# pt100.net
KiCad netlist of a schematic drawn in Altium Designer
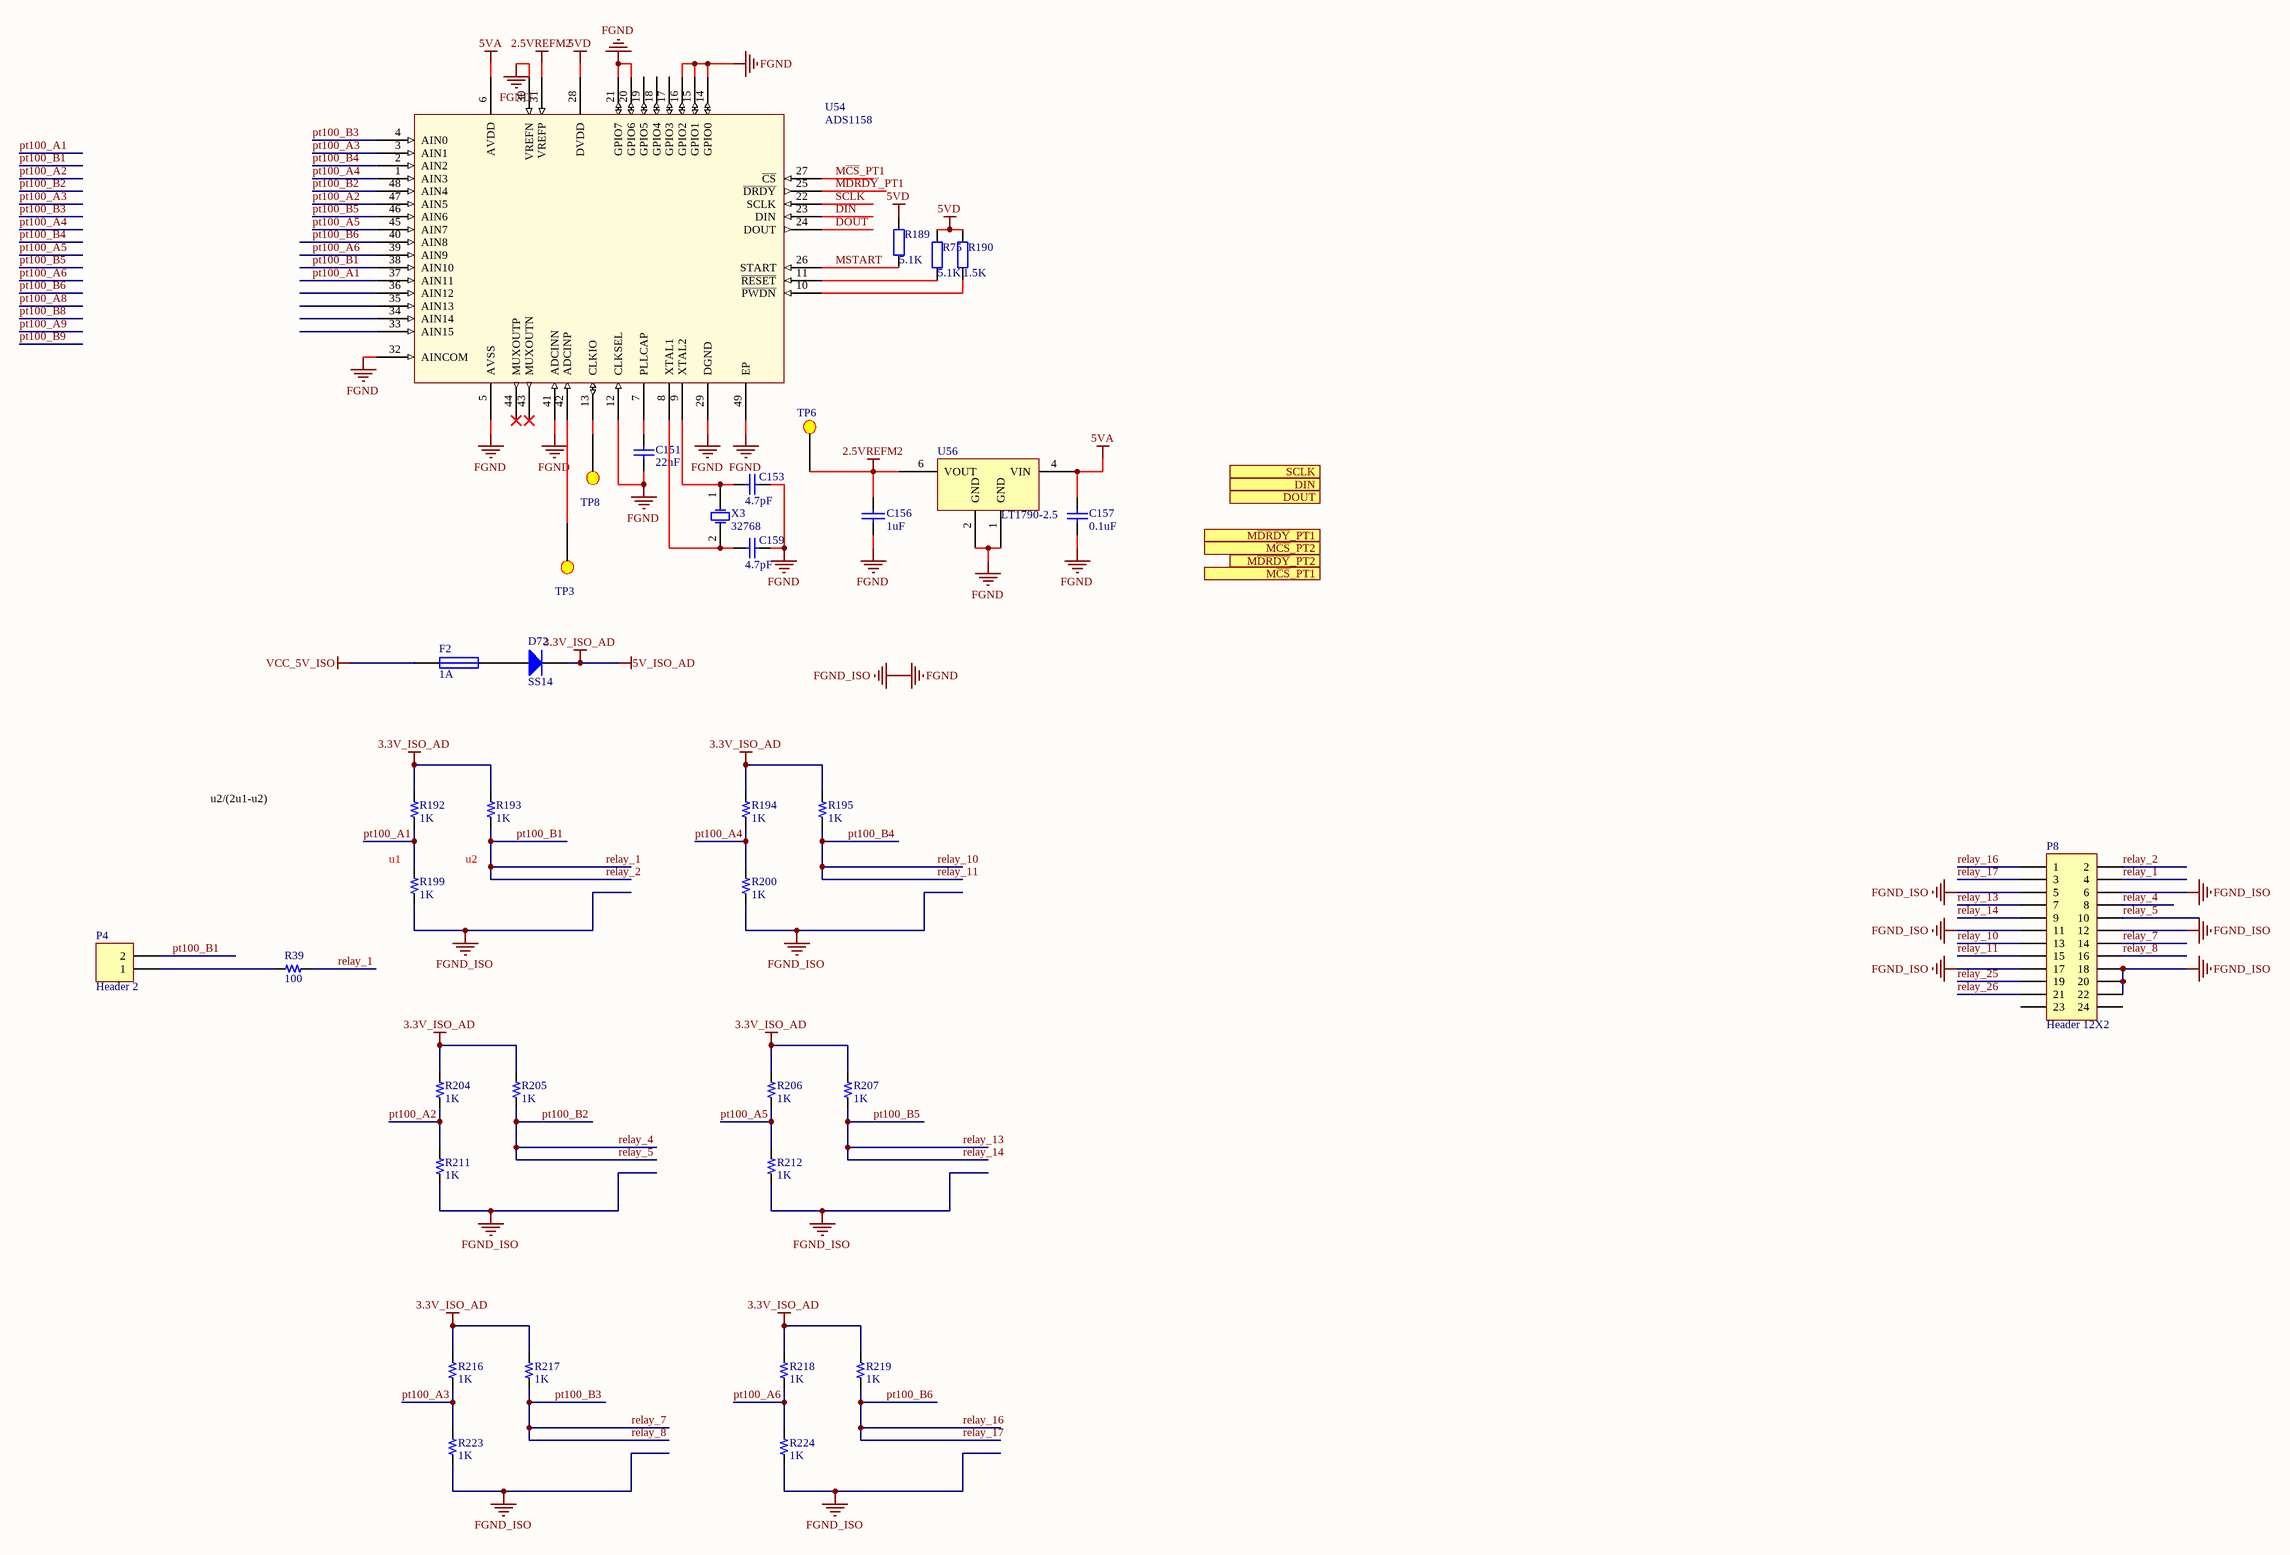
[diagram p0: pt100.SchDoc]

(export (version "E")
  (design (tool "Eeschema 10.0.6"))
  (components
    (comp (ref "C151")
      (value "22nF")
      (footprint "0805C")
      (description "Capacitor")
      (fields (field (name "PUBLISHER") "Altium Limited"))
      (libsource (lib "Miscellaneous Devices") (part "Cap"))
    )
    (comp (ref "C153")
      (value "4.7pF")
      (footprint "0603C")
      (description "Capacitor")
      (fields (field (name "PUBLISHER") "Altium Limited"))
      (libsource (lib "Miscellaneous Devices") (part "Cap"))
    )
    (comp (ref "C156")
      (value "1uF")
      (footprint "0603C")
      (description "Capacitor")
      (libsource (lib "*") (part "CAP"))
    )
    (comp (ref "C157")
      (value "0.1uF")
      (footprint "0603C")
      (description "Capacitor")
      (fields (field (name "PUBLISHER") "Altium Limited"))
      (libsource (lib "Miscellaneous Devices") (part "Cap"))
    )
    (comp (ref "C159")
      (value "4.7pF")
      (footprint "0603C")
      (description "Capacitor")
      (fields (field (name "PUBLISHER") "Altium Limited"))
      (libsource (lib "Miscellaneous Devices") (part "Cap"))
    )
    (comp (ref "D72")
      (value "SS14")
      (footprint "DO-214AC")
      (description "Default Diode")
      (fields (field (name "PUBLISHER") "Altium Limited"))
      (libsource (lib "Miscellaneous Devices") (part "Diode"))
    )
    (comp (ref "F2")
      (value "1A")
      (footprint "0805r")
      (description "Fuse")
      (fields (field (name "PUBLISHER") "Altium Limited"))
      (libsource (lib "Miscellaneous Devices") (part "Fuse 1"))
    )
    (comp (ref "P4")
      (value "Header 2")
      (footprint "HDR1X2")
      (description "Header, 2-Pin")
      (fields (field (name "PUBLISHER") "Altium Limited"))
      (libsource (lib "Miscellaneous Connectors") (part "Header 2"))
    )
    (comp (ref "P8")
      (value "Header 12X2")
      (footprint "controller_V1.1:XH2.54_2x12")
      (description "Header, 12-Pin, Dual row")
      (fields (field (name "PUBLISHER") "Altium Limited"))
      (libsource (lib "Miscellaneous Connectors") (part "Header 12X2"))
    )
    (comp (ref "R39")
      (value "100")
      (footprint "0603R")
      (description "R")
      (libsource (lib "JRJ_1") (part "R"))
    )
    (comp (ref "R75") (value "5.1K") (footprint "0603R") (libsource (lib "MQlibrary") (part "Res0805M")))
    (comp (ref "R189") (value "5.1K") (footprint "0603R") (libsource (lib "MQlibrary") (part "Res0805M")))
    (comp (ref "R190") (value "1.5K") (footprint "0603R") (libsource (lib "MQlibrary") (part "Res0805M")))
    (comp (ref "R192")
      (value "1K")
      (footprint "0603R")
      (description "R")
      (libsource (lib "JRJ_1") (part "R"))
    )
    (comp (ref "R193")
      (value "1K")
      (footprint "0603R")
      (description "R")
      (libsource (lib "JRJ_1") (part "R"))
    )
    (comp (ref "R194")
      (value "1K")
      (footprint "0603R")
      (description "R")
      (libsource (lib "JRJ_1") (part "R"))
    )
    (comp (ref "R195")
      (value "1K")
      (footprint "0603R")
      (description "R")
      (libsource (lib "JRJ_1") (part "R"))
    )
    (comp (ref "R199")
      (value "1K")
      (footprint "0603R")
      (description "R")
      (libsource (lib "JRJ_1") (part "R"))
    )
    (comp (ref "R200")
      (value "1K")
      (footprint "0603R")
      (description "R")
      (libsource (lib "JRJ_1") (part "R"))
    )
    (comp (ref "R204")
      (value "1K")
      (footprint "0603R")
      (description "R")
      (libsource (lib "JRJ_1") (part "R"))
    )
    (comp (ref "R205")
      (value "1K")
      (footprint "0603R")
      (description "R")
      (libsource (lib "JRJ_1") (part "R"))
    )
    (comp (ref "R206")
      (value "1K")
      (footprint "0603R")
      (description "R")
      (libsource (lib "JRJ_1") (part "R"))
    )
    (comp (ref "R207")
      (value "1K")
      (footprint "0603R")
      (description "R")
      (libsource (lib "JRJ_1") (part "R"))
    )
    (comp (ref "R211")
      (value "1K")
      (footprint "0603R")
      (description "R")
      (libsource (lib "JRJ_1") (part "R"))
    )
    (comp (ref "R212")
      (value "1K")
      (footprint "0603R")
      (description "R")
      (libsource (lib "JRJ_1") (part "R"))
    )
    (comp (ref "R216")
      (value "1K")
      (footprint "0603R")
      (description "R")
      (libsource (lib "JRJ_1") (part "R"))
    )
    (comp (ref "R217")
      (value "1K")
      (footprint "0603R")
      (description "R")
      (libsource (lib "JRJ_1") (part "R"))
    )
    (comp (ref "R218")
      (value "1K")
      (footprint "0603R")
      (description "R")
      (libsource (lib "JRJ_1") (part "R"))
    )
    (comp (ref "R219")
      (value "1K")
      (footprint "0603R")
      (description "R")
      (libsource (lib "JRJ_1") (part "R"))
    )
    (comp (ref "R223")
      (value "1K")
      (footprint "0603R")
      (description "R")
      (libsource (lib "JRJ_1") (part "R"))
    )
    (comp (ref "R224")
      (value "1K")
      (footprint "0603R")
      (description "R")
      (libsource (lib "JRJ_1") (part "R"))
    )
    (comp (ref "TP3")
      (value "TEST_POINT")
      (footprint "TPD")
      (libsource (lib "基带芯片OEM板_V1P0_张猛_20120921") (part "TEST_POINT"))
    )
    (comp (ref "TP6")
      (value "TEST_POINT")
      (footprint "TPD")
      (libsource (lib "基带芯片OEM板_V1P0_张猛_20120921") (part "TEST_POINT"))
    )
    (comp (ref "TP8")
      (value "TEST_POINT")
      (footprint "TPD")
      (libsource (lib "基带芯片OEM板_V1P0_张猛_20120921") (part "TEST_POINT"))
    )
    (comp (ref "U54")
      (value "ADS1158")
      (footprint "S-PVFQN-N48")
      (description "16-Channel, 16-Bit Analog-to-Digital Converter")
      (libsource (lib "Schlib") (part "ADS1158"))
    )
    (comp (ref "U56")
      (value "LT1790-2.5")
      (footprint "SOT23-6")
      (description "2.5V Micropower SOT-23  Low Dropout Reference")
      (libsource (lib "Schlib") (part "LT1790-2.5"))
    )
    (comp (ref "X3")
      (value "32768")
      (footprint "A")
      (description "Crystal Oscillator")
      (fields (field (name "PUBLISHER") "Altium Limited"))
      (libsource (lib "Miscellaneous Devices") (part "XTAL"))
    )
  )
  (nets
    (net (code "1") (name "/DIN") (class "Default")
      (node (ref "U54") (pin "23") (pinfunction "DIN_23") (pintype "input"))
    )
    (net (code "2") (name "/DOUT") (class "Default")
      (node (ref "U54") (pin "24") (pinfunction "DOUT_24") (pintype "output"))
    )
    (net (code "3") (name "/MSTART") (class "Default")
      (node (ref "R189") (pin "2") (pinfunction "2_2") (pintype "passive"))
      (node (ref "U54") (pin "26") (pinfunction "START_26") (pintype "input"))
    )
    (net (code "4") (name "/M~{CS}_PT1") (class "Default")
      (node (ref "U54") (pin "27") (pinfunction "~{CS}_27") (pintype "input"))
    )
    (net (code "6") (name "/M~{DRDY}_PT1") (class "Default")
      (node (ref "U54") (pin "25") (pinfunction "~{DRDY}_25") (pintype "output"))
    )
    (net (code "8") (name "/SCLK") (class "Default")
      (node (ref "U54") (pin "22") (pinfunction "SCLK_22") (pintype "input"))
    )
    (net (code "9") (name "/pt100_A1") (class "Default")
      (node (ref "R192") (pin "1") (pintype "passive"))
      (node (ref "R199") (pin "2") (pintype "passive"))
      (node (ref "U54") (pin "37") (pinfunction "AIN11_37") (pintype "input"))
    )
    (net (code "10") (name "/pt100_A2") (class "Default")
      (node (ref "R204") (pin "1") (pintype "passive"))
      (node (ref "R211") (pin "2") (pintype "passive"))
      (node (ref "U54") (pin "47") (pinfunction "AIN5_47") (pintype "input"))
    )
    (net (code "11") (name "/pt100_A3") (class "Default")
      (node (ref "R216") (pin "1") (pintype "passive"))
      (node (ref "R223") (pin "2") (pintype "passive"))
      (node (ref "U54") (pin "3") (pinfunction "AIN1_3") (pintype "input"))
    )
    (net (code "12") (name "/pt100_A4") (class "Default")
      (node (ref "R194") (pin "1") (pintype "passive"))
      (node (ref "R200") (pin "2") (pintype "passive"))
      (node (ref "U54") (pin "1") (pinfunction "AIN3_1") (pintype "input"))
    )
    (net (code "13") (name "/pt100_A5") (class "Default")
      (node (ref "R206") (pin "1") (pintype "passive"))
      (node (ref "R212") (pin "2") (pintype "passive"))
      (node (ref "U54") (pin "45") (pinfunction "AIN7_45") (pintype "input"))
    )
    (net (code "14") (name "/pt100_A6") (class "Default")
      (node (ref "R218") (pin "1") (pintype "passive"))
      (node (ref "R224") (pin "2") (pintype "passive"))
      (node (ref "U54") (pin "39") (pinfunction "AIN9_39") (pintype "input"))
    )
    (net (code "17") (name "/pt100_B1") (class "Default")
      (node (ref "P4") (pin "2") (pinfunction "2_2") (pintype "passive"))
      (node (ref "P8") (pin "2") (pinfunction "2_2") (pintype "passive"))
      (node (ref "P8") (pin "4") (pinfunction "4_4") (pintype "passive"))
      (node (ref "R193") (pin "1") (pintype "passive"))
      (node (ref "R39") (pin "1") (pintype "passive"))
      (node (ref "U54") (pin "38") (pinfunction "AIN10_38") (pintype "input"))
    )
    (net (code "18") (name "/pt100_B2") (class "Default")
      (node (ref "P8") (pin "10") (pinfunction "10_10") (pintype "passive"))
      (node (ref "P8") (pin "8") (pinfunction "8_8") (pintype "passive"))
      (node (ref "R205") (pin "1") (pintype "passive"))
      (node (ref "U54") (pin "48") (pinfunction "AIN4_48") (pintype "input"))
    )
    (net (code "19") (name "/pt100_B3") (class "Default")
      (node (ref "P8") (pin "14") (pinfunction "14_14") (pintype "passive"))
      (node (ref "P8") (pin "16") (pinfunction "16_16") (pintype "passive"))
      (node (ref "R217") (pin "1") (pintype "passive"))
      (node (ref "U54") (pin "4") (pinfunction "AIN0_4") (pintype "input"))
    )
    (net (code "20") (name "/pt100_B4") (class "Default")
      (node (ref "P8") (pin "13") (pinfunction "13_13") (pintype "passive"))
      (node (ref "P8") (pin "15") (pinfunction "15_15") (pintype "passive"))
      (node (ref "R195") (pin "1") (pintype "passive"))
      (node (ref "U54") (pin "2") (pinfunction "AIN2_2") (pintype "input"))
    )
    (net (code "21") (name "/pt100_B5") (class "Default")
      (node (ref "P8") (pin "7") (pinfunction "7_7") (pintype "passive"))
      (node (ref "P8") (pin "9") (pinfunction "9_9") (pintype "passive"))
      (node (ref "R207") (pin "1") (pintype "passive"))
      (node (ref "U54") (pin "46") (pinfunction "AIN6_46") (pintype "input"))
    )
    (net (code "22") (name "/pt100_B6") (class "Default")
      (node (ref "P8") (pin "1") (pinfunction "1_1") (pintype "passive"))
      (node (ref "P8") (pin "3") (pinfunction "3_3") (pintype "passive"))
      (node (ref "R219") (pin "1") (pintype "passive"))
      (node (ref "U54") (pin "40") (pinfunction "AIN8_40") (pintype "input"))
    )
    (net (code "25") (name "/relay_25") (class "Default")
      (node (ref "P8") (pin "19") (pinfunction "19_19") (pintype "passive"))
    )
    (net (code "26") (name "/relay_26") (class "Default")
      (node (ref "P8") (pin "21") (pinfunction "21_21") (pintype "passive"))
    )
    (net (code "27") (name "2.5VREFM2") (class "Default")
      (node (ref "C156") (pin "1") (pinfunction "1_1") (pintype "passive"))
      (node (ref "TP6") (pin "1") (pinfunction "1_1") (pintype "passive"))
      (node (ref "U54") (pin "31") (pinfunction "VREFP_31") (pintype "input"))
      (node (ref "U56") (pin "6") (pinfunction "VOUT_6") (pintype "power_in"))
    )
    (net (code "28") (name "3.3V_ISO_AD") (class "Default")
      (node (ref "D72") (pin "2") (pinfunction "K_2") (pintype "passive"))
      (node (ref "R192") (pin "2") (pintype "passive"))
      (node (ref "R193") (pin "2") (pintype "passive"))
      (node (ref "R194") (pin "2") (pintype "passive"))
      (node (ref "R195") (pin "2") (pintype "passive"))
      (node (ref "R204") (pin "2") (pintype "passive"))
      (node (ref "R205") (pin "2") (pintype "passive"))
      (node (ref "R206") (pin "2") (pintype "passive"))
      (node (ref "R207") (pin "2") (pintype "passive"))
      (node (ref "R216") (pin "2") (pintype "passive"))
      (node (ref "R217") (pin "2") (pintype "passive"))
      (node (ref "R218") (pin "2") (pintype "passive"))
      (node (ref "R219") (pin "2") (pintype "passive"))
    )
    (net (code "29") (name "5VA") (class "Default")
      (node (ref "C157") (pin "2") (pinfunction "2_2") (pintype "passive"))
      (node (ref "U54") (pin "6") (pinfunction "AVDD_6") (pintype "passive"))
      (node (ref "U56") (pin "4") (pinfunction "VIN_4") (pintype "power_in"))
    )
    (net (code "30") (name "5VD") (class "Default")
      (node (ref "R189") (pin "1") (pinfunction "1_1") (pintype "passive"))
      (node (ref "R190") (pin "1") (pinfunction "1_1") (pintype "passive"))
      (node (ref "R75") (pin "1") (pinfunction "1_1") (pintype "passive"))
      (node (ref "U54") (pin "28") (pinfunction "DVDD_28") (pintype "power_in"))
    )
    (net (code "31") (name "FGND") (class "Default")
      (node (ref "C151") (pin "2") (pinfunction "2_2") (pintype "passive"))
      (node (ref "C153") (pin "2") (pinfunction "2_2") (pintype "passive"))
      (node (ref "C156") (pin "2") (pinfunction "2_2") (pintype "passive"))
      (node (ref "C157") (pin "1") (pinfunction "1_1") (pintype "passive"))
      (node (ref "C159") (pin "2") (pinfunction "2_2") (pintype "passive"))
      (node (ref "P8") (pin "11") (pinfunction "11_11") (pintype "passive"))
      (node (ref "P8") (pin "12") (pinfunction "12_12") (pintype "passive"))
      (node (ref "P8") (pin "17") (pinfunction "17_17") (pintype "passive"))
      (node (ref "P8") (pin "18") (pinfunction "18_18") (pintype "passive"))
      (node (ref "P8") (pin "20") (pinfunction "20_20") (pintype "passive"))
      (node (ref "P8") (pin "22") (pinfunction "22_22") (pintype "passive"))
      (node (ref "P8") (pin "5") (pinfunction "5_5") (pintype "passive"))
      (node (ref "P8") (pin "6") (pinfunction "6_6") (pintype "passive"))
      (node (ref "R199") (pin "1") (pintype "passive"))
      (node (ref "R200") (pin "1") (pintype "passive"))
      (node (ref "R211") (pin "1") (pintype "passive"))
      (node (ref "R212") (pin "1") (pintype "passive"))
      (node (ref "R223") (pin "1") (pintype "passive"))
      (node (ref "R224") (pin "1") (pintype "passive"))
      (node (ref "U54") (pin "12") (pinfunction "CLKSEL_12") (pintype "input"))
      (node (ref "U54") (pin "14") (pinfunction "GPIO0_14") (pintype "bidirectional"))
      (node (ref "U54") (pin "15") (pinfunction "GPIO1_15") (pintype "bidirectional"))
      (node (ref "U54") (pin "16") (pinfunction "GPIO2_16") (pintype "bidirectional"))
      (node (ref "U54") (pin "20") (pinfunction "GPIO6_20") (pintype "bidirectional"))
      (node (ref "U54") (pin "21") (pinfunction "GPIO7_21") (pintype "bidirectional"))
      (node (ref "U54") (pin "29") (pinfunction "DGND_29") (pintype "power_in"))
      (node (ref "U54") (pin "30") (pinfunction "VREFN_30") (pintype "input"))
      (node (ref "U54") (pin "32") (pinfunction "AINCOM_32") (pintype "input"))
      (node (ref "U54") (pin "41") (pinfunction "ADCINN_41") (pintype "input"))
      (node (ref "U54") (pin "49") (pinfunction "EP_49") (pintype "passive"))
      (node (ref "U54") (pin "5") (pinfunction "AVSS_5") (pintype "power_in"))
      (node (ref "U56") (pin "1") (pinfunction "GND_1") (pintype "power_in"))
      (node (ref "U56") (pin "2") (pinfunction "GND_2") (pintype "power_in"))
    )
    (net (code "32") (name "Net-(D72-A)") (class "Default")
      (node (ref "D72") (pin "1") (pinfunction "A_1") (pintype "passive"))
      (node (ref "F2") (pin "2") (pinfunction "2_2") (pintype "passive"))
    )
    (net (code "33") (name "Net-(P4-Pad1)") (class "Default")
      (node (ref "P4") (pin "1") (pinfunction "1_1") (pintype "passive"))
      (node (ref "R39") (pin "2") (pintype "passive"))
    )
    (net (code "34") (name "Net-(U54-ADCINP)") (class "Default")
      (node (ref "TP3") (pin "1") (pinfunction "1_1") (pintype "passive"))
      (node (ref "U54") (pin "42") (pinfunction "ADCINP_42") (pintype "input"))
    )
    (net (code "35") (name "Net-(U54-CLKIO)") (class "Default")
      (node (ref "TP8") (pin "1") (pinfunction "1_1") (pintype "passive"))
      (node (ref "U54") (pin "13") (pinfunction "CLKIO_13") (pintype "bidirectional"))
    )
    (net (code "36") (name "Net-(U54-PLLCAP)") (class "Default")
      (node (ref "C151") (pin "1") (pinfunction "1_1") (pintype "passive"))
      (node (ref "U54") (pin "7") (pinfunction "PLLCAP_7") (pintype "power_in"))
    )
    (net (code "37") (name "Net-(U54-XTAL1)") (class "Default")
      (node (ref "C159") (pin "1") (pinfunction "1_1") (pintype "passive"))
      (node (ref "U54") (pin "8") (pinfunction "XTAL1_8") (pintype "passive"))
      (node (ref "X3") (pin "2") (pinfunction "OSC2_2") (pintype "passive"))
    )
    (net (code "38") (name "Net-(U54-XTAL2)") (class "Default")
      (node (ref "C153") (pin "1") (pinfunction "1_1") (pintype "passive"))
      (node (ref "U54") (pin "9") (pinfunction "XTAL2_9") (pintype "passive"))
      (node (ref "X3") (pin "1") (pinfunction "OSC1_1") (pintype "passive"))
    )
    (net (code "39") (name "Net-(U54-~{PWDN})") (class "Default")
      (node (ref "R190") (pin "2") (pinfunction "2_2") (pintype "passive"))
      (node (ref "U54") (pin "10") (pinfunction "~{PWDN}_10") (pintype "input"))
    )
    (net (code "40") (name "Net-(U54-~{RESET})") (class "Default")
      (node (ref "R75") (pin "2") (pinfunction "2_2") (pintype "passive"))
      (node (ref "U54") (pin "11") (pinfunction "~{RESET}_11") (pintype "input"))
    )
    (net (code "41") (name "VCC_5V_ISO") (class "Default")
      (node (ref "F2") (pin "1") (pinfunction "1_1") (pintype "passive"))
    )
    (net (code "42") (name "unconnected-(P8-Pad23)") (class "Default")
      (node (ref "P8") (pin "23") (pinfunction "23_23") (pintype "passive"))
    )
    (net (code "43") (name "unconnected-(P8-Pad24)") (class "Default")
      (node (ref "P8") (pin "24") (pinfunction "24_24") (pintype "passive"))
    )
    (net (code "44") (name "unconnected-(U54-AIN12-Pad36)") (class "Default")
      (node (ref "U54") (pin "36") (pinfunction "AIN12_36") (pintype "input"))
    )
    (net (code "45") (name "unconnected-(U54-AIN13-Pad35)") (class "Default")
      (node (ref "U54") (pin "35") (pinfunction "AIN13_35") (pintype "input"))
    )
    (net (code "46") (name "unconnected-(U54-AIN14-Pad34)") (class "Default")
      (node (ref "U54") (pin "34") (pinfunction "AIN14_34") (pintype "input"))
    )
    (net (code "47") (name "unconnected-(U54-AIN15-Pad33)") (class "Default")
      (node (ref "U54") (pin "33") (pinfunction "AIN15_33") (pintype "input"))
    )
    (net (code "48") (name "unconnected-(U54-GPIO3-Pad17)") (class "Default")
      (node (ref "U54") (pin "17") (pinfunction "GPIO3_17") (pintype "bidirectional"))
    )
    (net (code "49") (name "unconnected-(U54-GPIO4-Pad18)") (class "Default")
      (node (ref "U54") (pin "18") (pinfunction "GPIO4_18") (pintype "bidirectional"))
    )
    (net (code "50") (name "unconnected-(U54-GPIO5-Pad19)") (class "Default")
      (node (ref "U54") (pin "19") (pinfunction "GPIO5_19") (pintype "bidirectional"))
    )
    (net (code "51") (name "unconnected-(U54-MUXOUTN-Pad43)") (class "Default")
      (node (ref "U54") (pin "43") (pinfunction "MUXOUTN_43") (pintype "output+no_connect"))
    )
    (net (code "52") (name "unconnected-(U54-MUXOUTP-Pad44)") (class "Default")
      (node (ref "U54") (pin "44") (pinfunction "MUXOUTP_44") (pintype "output+no_connect"))
    )
    (net (code "53") (name "unconnected-(U56-DNC-Pad3)") (class "Default")
      (node (ref "U56") (pin "3") (pinfunction "DNC_3") (pintype "passive"))
    )
    (net (code "54") (name "unconnected-(U56-DNC-Pad5)") (class "Default")
      (node (ref "U56") (pin "5") (pinfunction "DNC_5") (pintype "passive"))
    )
  )
)
